# R650C.net
KiCad netlist of a schematic drawn in EAGLE
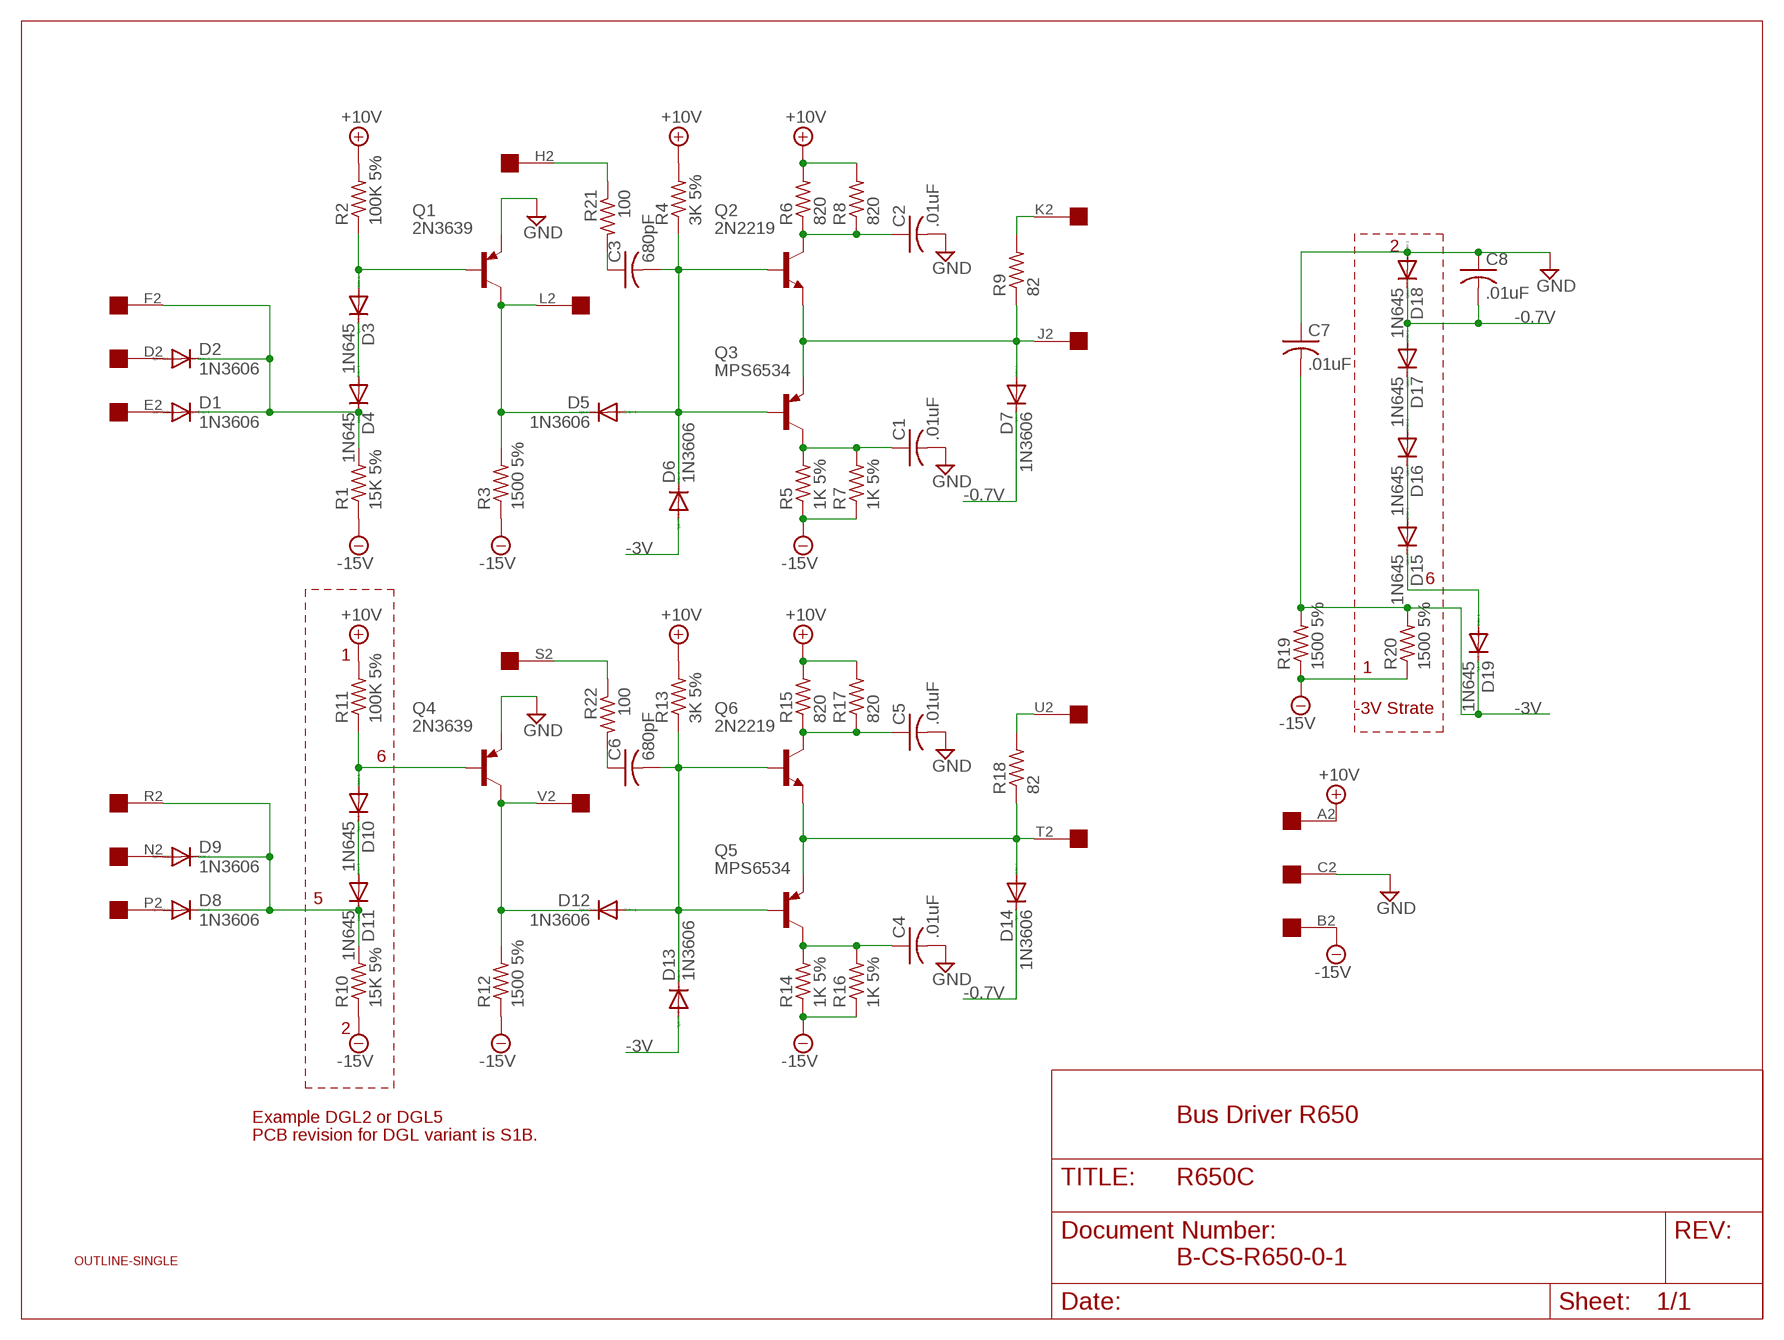
[diagram p0: schematic, sheet 1]

(export (version "E")
  (design (tool "Eeschema 10.0.6"))
  (components
    (comp (ref "C1")
      (value ".01uF")
      (footprint "eagle-import:C050-025X075")
      (libsource (lib "eagle-import") (part "C-US050-025X075"))
    )
    (comp (ref "C2")
      (value ".01uF")
      (footprint "eagle-import:C050-025X075")
      (libsource (lib "eagle-import") (part "C-US050-025X075"))
    )
    (comp (ref "C3")
      (value "680pF")
      (footprint "eagle-import:C050-025X075")
      (libsource (lib "eagle-import") (part "C-US050-025X075"))
    )
    (comp (ref "C4")
      (value ".01uF")
      (footprint "eagle-import:C050-025X075")
      (libsource (lib "eagle-import") (part "C-US050-025X075"))
    )
    (comp (ref "C5")
      (value ".01uF")
      (footprint "eagle-import:C050-025X075")
      (libsource (lib "eagle-import") (part "C-US050-025X075"))
    )
    (comp (ref "C6")
      (value "680pF")
      (footprint "eagle-import:C050-025X075")
      (libsource (lib "eagle-import") (part "C-US050-025X075"))
    )
    (comp (ref "C7")
      (value ".01uF")
      (footprint "eagle-import:C050-025X075")
      (libsource (lib "eagle-import") (part "C-US050-025X075"))
    )
    (comp (ref "C8")
      (value ".01uF")
      (footprint "eagle-import:C050-025X075")
      (libsource (lib "eagle-import") (part "C-US050-025X075"))
    )
    (comp (ref "D1")
      (value "1N3606")
      (footprint "eagle-import:DO35-10")
      (libsource (lib "eagle-import") (part "1N4148DO35-10"))
    )
    (comp (ref "D2")
      (value "1N3606")
      (footprint "eagle-import:DO35-10")
      (libsource (lib "eagle-import") (part "1N4148DO35-10"))
    )
    (comp (ref "D3")
      (value "1N645")
      (footprint "eagle-import:DO35-10")
      (libsource (lib "eagle-import") (part "1N4148DO35-10"))
    )
    (comp (ref "D4")
      (value "1N645")
      (footprint "eagle-import:DO35-10")
      (libsource (lib "eagle-import") (part "1N4148DO35-10"))
    )
    (comp (ref "D5")
      (value "1N3606")
      (footprint "eagle-import:DO35-10")
      (libsource (lib "eagle-import") (part "1N4148DO35-10"))
    )
    (comp (ref "D6")
      (value "1N3606")
      (footprint "eagle-import:DO35-10")
      (libsource (lib "eagle-import") (part "1N4148DO35-10"))
    )
    (comp (ref "D7")
      (value "1N3606")
      (footprint "eagle-import:DO35-10")
      (libsource (lib "eagle-import") (part "1N4148DO35-10"))
    )
    (comp (ref "D8")
      (value "1N3606")
      (footprint "eagle-import:DO35-10")
      (libsource (lib "eagle-import") (part "1N4148DO35-10"))
    )
    (comp (ref "D9")
      (value "1N3606")
      (footprint "eagle-import:DO35-10")
      (libsource (lib "eagle-import") (part "1N4148DO35-10"))
    )
    (comp (ref "D10")
      (value "1N645")
      (footprint "eagle-import:DO35-10")
      (libsource (lib "eagle-import") (part "1N4148DO35-10"))
    )
    (comp (ref "D11")
      (value "1N645")
      (footprint "eagle-import:DO35-10")
      (libsource (lib "eagle-import") (part "1N4148DO35-10"))
    )
    (comp (ref "D12")
      (value "1N3606")
      (footprint "eagle-import:DO35-10")
      (libsource (lib "eagle-import") (part "1N4148DO35-10"))
    )
    (comp (ref "D13")
      (value "1N3606")
      (footprint "eagle-import:DO35-10")
      (libsource (lib "eagle-import") (part "1N4148DO35-10"))
    )
    (comp (ref "D14")
      (value "1N3606")
      (footprint "eagle-import:DO35-10")
      (libsource (lib "eagle-import") (part "1N4148DO35-10"))
    )
    (comp (ref "D15")
      (value "1N645")
      (footprint "eagle-import:DO35-10")
      (libsource (lib "eagle-import") (part "1N4148DO35-10"))
    )
    (comp (ref "D16")
      (value "1N645")
      (footprint "eagle-import:DO35-10")
      (libsource (lib "eagle-import") (part "1N4148DO35-10"))
    )
    (comp (ref "D17")
      (value "1N645")
      (footprint "eagle-import:DO35-10")
      (libsource (lib "eagle-import") (part "1N4148DO35-10"))
    )
    (comp (ref "D18")
      (value "1N645")
      (footprint "eagle-import:DO35-10")
      (libsource (lib "eagle-import") (part "1N4148DO35-10"))
    )
    (comp (ref "D19")
      (value "1N645")
      (footprint "eagle-import:DO35-10")
      (libsource (lib "eagle-import") (part "1N4148DO35-10"))
    )
    (comp (ref "Q1")
      (value "2N3639")
      (footprint "eagle-import:TO39")
      (libsource (lib "eagle-import") (part "2N3637"))
    )
    (comp (ref "Q2")
      (value "2N2219")
      (footprint "eagle-import:TO5")
      (libsource (lib "eagle-import") (part "2N2219"))
    )
    (comp (ref "Q3")
      (value "MPS6534")
      (footprint "eagle-import:TO39")
      (libsource (lib "eagle-import") (part "2N3637"))
    )
    (comp (ref "Q4")
      (value "2N3639")
      (footprint "eagle-import:TO39")
      (libsource (lib "eagle-import") (part "2N3637"))
    )
    (comp (ref "Q5")
      (value "MPS6534")
      (footprint "eagle-import:TO39")
      (libsource (lib "eagle-import") (part "2N3637"))
    )
    (comp (ref "Q6")
      (value "2N2219")
      (footprint "eagle-import:TO5")
      (libsource (lib "eagle-import") (part "2N2219"))
    )
    (comp (ref "R1")
      (value "15K 5%")
      (footprint "eagle-import:0207_10")
      (libsource (lib "eagle-import") (part "R-US_0207/10"))
    )
    (comp (ref "R2")
      (value "100K 5%")
      (footprint "eagle-import:0207_10")
      (libsource (lib "eagle-import") (part "R-US_0207/10"))
    )
    (comp (ref "R3")
      (value "1500 5%")
      (footprint "eagle-import:0207_10")
      (libsource (lib "eagle-import") (part "R-US_0207/10"))
    )
    (comp (ref "R4")
      (value "3K 5%")
      (footprint "eagle-import:0207_10")
      (libsource (lib "eagle-import") (part "R-US_0207/10"))
    )
    (comp (ref "R5")
      (value "1K 5%")
      (footprint "eagle-import:0207_10")
      (libsource (lib "eagle-import") (part "R-US_0207/10"))
    )
    (comp (ref "R6")
      (value "820")
      (footprint "eagle-import:0207_10")
      (libsource (lib "eagle-import") (part "R-US_0207/10"))
    )
    (comp (ref "R7")
      (value "1K 5%")
      (footprint "eagle-import:0207_10")
      (libsource (lib "eagle-import") (part "R-US_0207/10"))
    )
    (comp (ref "R8")
      (value "820")
      (footprint "eagle-import:0207_10")
      (libsource (lib "eagle-import") (part "R-US_0207/10"))
    )
    (comp (ref "R9")
      (value "82")
      (footprint "eagle-import:0207_10")
      (libsource (lib "eagle-import") (part "R-US_0207/10"))
    )
    (comp (ref "R10")
      (value "15K 5%")
      (footprint "eagle-import:0207_10")
      (libsource (lib "eagle-import") (part "R-US_0207/10"))
    )
    (comp (ref "R11")
      (value "100K 5%")
      (footprint "eagle-import:0207_10")
      (libsource (lib "eagle-import") (part "R-US_0207/10"))
    )
    (comp (ref "R12")
      (value "1500 5%")
      (footprint "eagle-import:0207_10")
      (libsource (lib "eagle-import") (part "R-US_0207/10"))
    )
    (comp (ref "R13")
      (value "3K 5%")
      (footprint "eagle-import:0207_10")
      (libsource (lib "eagle-import") (part "R-US_0207/10"))
    )
    (comp (ref "R14")
      (value "1K 5%")
      (footprint "eagle-import:0207_10")
      (libsource (lib "eagle-import") (part "R-US_0207/10"))
    )
    (comp (ref "R15")
      (value "820")
      (footprint "eagle-import:0207_10")
      (libsource (lib "eagle-import") (part "R-US_0207/10"))
    )
    (comp (ref "R16")
      (value "1K 5%")
      (footprint "eagle-import:0207_10")
      (libsource (lib "eagle-import") (part "R-US_0207/10"))
    )
    (comp (ref "R17")
      (value "820")
      (footprint "eagle-import:0207_10")
      (libsource (lib "eagle-import") (part "R-US_0207/10"))
    )
    (comp (ref "R18")
      (value "82")
      (footprint "eagle-import:0207_10")
      (libsource (lib "eagle-import") (part "R-US_0207/10"))
    )
    (comp (ref "R19")
      (value "1500 5%")
      (footprint "eagle-import:0207_10")
      (libsource (lib "eagle-import") (part "R-US_0207/10"))
    )
    (comp (ref "R20")
      (value "1500 5%")
      (footprint "eagle-import:0207_10")
      (libsource (lib "eagle-import") (part "R-US_0207/10"))
    )
    (comp (ref "R21")
      (value "100")
      (footprint "eagle-import:0207_10")
      (libsource (lib "eagle-import") (part "R-US_0207/10"))
    )
    (comp (ref "R22")
      (value "100")
      (footprint "eagle-import:0207_10")
      (libsource (lib "eagle-import") (part "R-US_0207/10"))
    )
    (comp (ref "U$1")
      (value "OUTLINE-SINGLE")
      (footprint "eagle-import:SINGLE")
      (libsource (lib "eagle-import") (part "OUTLINE-SINGLE"))
    )
    (comp (ref "U$2")
      (value "EDGE-1")
      (footprint "eagle-import:EDGE-CON1")
      (libsource (lib "eagle-import") (part "EDGE-1"))
    )
  )
  (nets
    (net (code "1") (name "+10V") (class "Default")
      (node (ref "R11") (pin "2") (pinfunction "2_2") (pintype "passive"))
      (node (ref "R13") (pin "2") (pinfunction "2_2") (pintype "passive"))
      (node (ref "R15") (pin "2") (pinfunction "2_2") (pintype "passive"))
      (node (ref "R17") (pin "2") (pinfunction "2_2") (pintype "passive"))
      (node (ref "R2") (pin "2") (pinfunction "2_2") (pintype "passive"))
      (node (ref "R4") (pin "2") (pinfunction "2_2") (pintype "passive"))
      (node (ref "R6") (pin "2") (pinfunction "2_2") (pintype "passive"))
      (node (ref "R8") (pin "2") (pinfunction "2_2") (pintype "passive"))
      (node (ref "U$2") (pin "A2") (pinfunction "1_A2") (pintype "bidirectional"))
    )
    (net (code "2") (name "-15V") (class "Default")
      (node (ref "R1") (pin "1") (pinfunction "1_1") (pintype "passive"))
      (node (ref "R10") (pin "1") (pinfunction "1_1") (pintype "passive"))
      (node (ref "R12") (pin "1") (pinfunction "1_1") (pintype "passive"))
      (node (ref "R14") (pin "1") (pinfunction "1_1") (pintype "passive"))
      (node (ref "R16") (pin "1") (pinfunction "1_1") (pintype "passive"))
      (node (ref "R19") (pin "1") (pinfunction "1_1") (pintype "passive"))
      (node (ref "R20") (pin "1") (pinfunction "1_1") (pintype "passive"))
      (node (ref "R3") (pin "1") (pinfunction "1_1") (pintype "passive"))
      (node (ref "R5") (pin "1") (pinfunction "1_1") (pintype "passive"))
      (node (ref "R7") (pin "1") (pinfunction "1_1") (pintype "passive"))
      (node (ref "U$2") (pin "B2") (pinfunction "1_B2") (pintype "bidirectional"))
    )
    (net (code "3") (name "/-0.7V") (class "Default")
      (node (ref "C8") (pin "2") (pinfunction "2_2") (pintype "passive"))
      (node (ref "D14") (pin "C") (pinfunction "C_C") (pintype "passive"))
      (node (ref "D17") (pin "A") (pinfunction "A_A") (pintype "passive"))
      (node (ref "D18") (pin "C") (pinfunction "C_C") (pintype "passive"))
      (node (ref "D7") (pin "C") (pinfunction "C_C") (pintype "passive"))
    )
    (net (code "4") (name "/-3V") (class "Default")
      (node (ref "C7") (pin "2") (pinfunction "2_2") (pintype "passive"))
      (node (ref "D13") (pin "A") (pinfunction "A_A") (pintype "passive"))
      (node (ref "D19") (pin "C") (pinfunction "C_C") (pintype "passive"))
      (node (ref "D6") (pin "A") (pinfunction "A_A") (pintype "passive"))
      (node (ref "R19") (pin "2") (pinfunction "2_2") (pintype "passive"))
      (node (ref "R20") (pin "2") (pinfunction "2_2") (pintype "passive"))
    )
    (net (code "5") (name "GND") (class "Default")
      (node (ref "C1") (pin "2") (pinfunction "2_2") (pintype "passive"))
      (node (ref "C2") (pin "2") (pinfunction "2_2") (pintype "passive"))
      (node (ref "C4") (pin "2") (pinfunction "2_2") (pintype "passive"))
      (node (ref "C5") (pin "2") (pinfunction "2_2") (pintype "passive"))
      (node (ref "C7") (pin "1") (pinfunction "1_1") (pintype "passive"))
      (node (ref "C8") (pin "1") (pinfunction "1_1") (pintype "passive"))
      (node (ref "D18") (pin "A") (pinfunction "A_A") (pintype "passive"))
      (node (ref "Q1") (pin "1") (pinfunction "E_1") (pintype "passive"))
      (node (ref "Q4") (pin "1") (pinfunction "E_1") (pintype "passive"))
      (node (ref "U$2") (pin "C2") (pinfunction "1_C2") (pintype "bidirectional"))
    )
    (net (code "6") (name "Net-(C3-Pad1)") (class "Default")
      (node (ref "C3") (pin "1") (pinfunction "1_1") (pintype "passive"))
      (node (ref "R21") (pin "2") (pinfunction "2_2") (pintype "passive"))
    )
    (net (code "7") (name "Net-(C6-Pad1)") (class "Default")
      (node (ref "C6") (pin "1") (pinfunction "1_1") (pintype "passive"))
      (node (ref "R22") (pin "2") (pinfunction "2_2") (pintype "passive"))
    )
    (net (code "8") (name "Net-(D3-PadC)") (class "Default")
      (node (ref "D3") (pin "C") (pinfunction "C_C") (pintype "passive"))
      (node (ref "D4") (pin "A") (pinfunction "A_A") (pintype "passive"))
    )
    (net (code "9") (name "Net-(D10-PadC)") (class "Default")
      (node (ref "D10") (pin "C") (pinfunction "C_C") (pintype "passive"))
      (node (ref "D11") (pin "A") (pinfunction "A_A") (pintype "passive"))
    )
    (net (code "10") (name "Net-(D15-PadA)") (class "Default")
      (node (ref "D15") (pin "A") (pinfunction "A_A") (pintype "passive"))
      (node (ref "D16") (pin "C") (pinfunction "C_C") (pintype "passive"))
    )
    (net (code "11") (name "Net-(D15-PadC)") (class "Default")
      (node (ref "D15") (pin "C") (pinfunction "C_C") (pintype "passive"))
      (node (ref "D19") (pin "A") (pinfunction "A_A") (pintype "passive"))
    )
    (net (code "12") (name "Net-(D16-PadA)") (class "Default")
      (node (ref "D16") (pin "A") (pinfunction "A_A") (pintype "passive"))
      (node (ref "D17") (pin "C") (pinfunction "C_C") (pintype "passive"))
    )
    (net (code "13") (name "Net-(Q1-B)") (class "Default")
      (node (ref "D3") (pin "A") (pinfunction "A_A") (pintype "passive"))
      (node (ref "Q1") (pin "2") (pinfunction "B_2") (pintype "passive"))
      (node (ref "R2") (pin "1") (pinfunction "1_1") (pintype "passive"))
    )
    (net (code "14") (name "Net-(Q1-C)") (class "Default")
      (node (ref "D5") (pin "C") (pinfunction "C_C") (pintype "passive"))
      (node (ref "Q1") (pin "3") (pinfunction "C_3") (pintype "passive"))
      (node (ref "R3") (pin "2") (pinfunction "2_2") (pintype "passive"))
      (node (ref "U$2") (pin "L2") (pinfunction "1_L2") (pintype "bidirectional"))
    )
    (net (code "15") (name "Net-(Q2-B)") (class "Default")
      (node (ref "C3") (pin "2") (pinfunction "2_2") (pintype "passive"))
      (node (ref "D5") (pin "A") (pinfunction "A_A") (pintype "passive"))
      (node (ref "D6") (pin "C") (pinfunction "C_C") (pintype "passive"))
      (node (ref "Q2") (pin "2") (pinfunction "B_2") (pintype "passive"))
      (node (ref "Q3") (pin "2") (pinfunction "B_2") (pintype "passive"))
      (node (ref "R4") (pin "1") (pinfunction "1_1") (pintype "passive"))
    )
    (net (code "16") (name "Net-(Q2-C)") (class "Default")
      (node (ref "C2") (pin "1") (pinfunction "1_1") (pintype "passive"))
      (node (ref "Q2") (pin "3") (pinfunction "C_3") (pintype "passive"))
      (node (ref "R6") (pin "1") (pinfunction "1_1") (pintype "passive"))
      (node (ref "R8") (pin "1") (pinfunction "1_1") (pintype "passive"))
    )
    (net (code "17") (name "Net-(Q2-E)") (class "Default")
      (node (ref "D7") (pin "A") (pinfunction "A_A") (pintype "passive"))
      (node (ref "Q2") (pin "1") (pinfunction "E_1") (pintype "passive"))
      (node (ref "Q3") (pin "1") (pinfunction "E_1") (pintype "passive"))
      (node (ref "R9") (pin "1") (pinfunction "1_1") (pintype "passive"))
      (node (ref "U$2") (pin "J2") (pinfunction "1_J2") (pintype "bidirectional"))
    )
    (net (code "18") (name "Net-(Q3-C)") (class "Default")
      (node (ref "C1") (pin "1") (pinfunction "1_1") (pintype "passive"))
      (node (ref "Q3") (pin "3") (pinfunction "C_3") (pintype "passive"))
      (node (ref "R5") (pin "2") (pinfunction "2_2") (pintype "passive"))
      (node (ref "R7") (pin "2") (pinfunction "2_2") (pintype "passive"))
    )
    (net (code "19") (name "Net-(Q4-B)") (class "Default")
      (node (ref "D10") (pin "A") (pinfunction "A_A") (pintype "passive"))
      (node (ref "Q4") (pin "2") (pinfunction "B_2") (pintype "passive"))
      (node (ref "R11") (pin "1") (pinfunction "1_1") (pintype "passive"))
    )
    (net (code "20") (name "Net-(Q4-C)") (class "Default")
      (node (ref "D12") (pin "C") (pinfunction "C_C") (pintype "passive"))
      (node (ref "Q4") (pin "3") (pinfunction "C_3") (pintype "passive"))
      (node (ref "R12") (pin "2") (pinfunction "2_2") (pintype "passive"))
      (node (ref "U$2") (pin "V2") (pinfunction "1_V2") (pintype "bidirectional"))
    )
    (net (code "21") (name "Net-(Q5-B)") (class "Default")
      (node (ref "C6") (pin "2") (pinfunction "2_2") (pintype "passive"))
      (node (ref "D12") (pin "A") (pinfunction "A_A") (pintype "passive"))
      (node (ref "D13") (pin "C") (pinfunction "C_C") (pintype "passive"))
      (node (ref "Q5") (pin "2") (pinfunction "B_2") (pintype "passive"))
      (node (ref "Q6") (pin "2") (pinfunction "B_2") (pintype "passive"))
      (node (ref "R13") (pin "1") (pinfunction "1_1") (pintype "passive"))
    )
    (net (code "22") (name "Net-(Q5-C)") (class "Default")
      (node (ref "C4") (pin "1") (pinfunction "1_1") (pintype "passive"))
      (node (ref "Q5") (pin "3") (pinfunction "C_3") (pintype "passive"))
      (node (ref "R14") (pin "2") (pinfunction "2_2") (pintype "passive"))
      (node (ref "R16") (pin "2") (pinfunction "2_2") (pintype "passive"))
    )
    (net (code "23") (name "Net-(Q5-E)") (class "Default")
      (node (ref "D14") (pin "A") (pinfunction "A_A") (pintype "passive"))
      (node (ref "Q5") (pin "1") (pinfunction "E_1") (pintype "passive"))
      (node (ref "Q6") (pin "1") (pinfunction "E_1") (pintype "passive"))
      (node (ref "R18") (pin "1") (pinfunction "1_1") (pintype "passive"))
      (node (ref "U$2") (pin "T2") (pinfunction "1_T2") (pintype "bidirectional"))
    )
    (net (code "24") (name "Net-(Q6-C)") (class "Default")
      (node (ref "C5") (pin "1") (pinfunction "1_1") (pintype "passive"))
      (node (ref "Q6") (pin "3") (pinfunction "C_3") (pintype "passive"))
      (node (ref "R15") (pin "1") (pinfunction "1_1") (pintype "passive"))
      (node (ref "R17") (pin "1") (pinfunction "1_1") (pintype "passive"))
    )
    (net (code "25") (name "Net-(U$2D-1)") (class "Default")
      (node (ref "D2") (pin "A") (pinfunction "A_A") (pintype "passive"))
      (node (ref "U$2") (pin "D2") (pinfunction "1_D2") (pintype "bidirectional"))
    )
    (net (code "26") (name "Net-(U$2E-1)") (class "Default")
      (node (ref "D1") (pin "A") (pinfunction "A_A") (pintype "passive"))
      (node (ref "U$2") (pin "E2") (pinfunction "1_E2") (pintype "bidirectional"))
    )
    (net (code "27") (name "Net-(U$2F-1)") (class "Default")
      (node (ref "D1") (pin "C") (pinfunction "C_C") (pintype "passive"))
      (node (ref "D2") (pin "C") (pinfunction "C_C") (pintype "passive"))
      (node (ref "D4") (pin "C") (pinfunction "C_C") (pintype "passive"))
      (node (ref "R1") (pin "2") (pinfunction "2_2") (pintype "passive"))
      (node (ref "U$2") (pin "F2") (pinfunction "1_F2") (pintype "bidirectional"))
    )
    (net (code "28") (name "Net-(U$2G-1)") (class "Default")
      (node (ref "R21") (pin "1") (pinfunction "1_1") (pintype "passive"))
      (node (ref "U$2") (pin "H2") (pinfunction "1_H2") (pintype "bidirectional"))
    )
    (net (code "29") (name "Net-(U$2I-1)") (class "Default")
      (node (ref "R9") (pin "2") (pinfunction "2_2") (pintype "passive"))
      (node (ref "U$2") (pin "K2") (pinfunction "1_K2") (pintype "bidirectional"))
    )
    (net (code "30") (name "Net-(U$2L-1)") (class "Default")
      (node (ref "D9") (pin "A") (pinfunction "A_A") (pintype "passive"))
      (node (ref "U$2") (pin "N2") (pinfunction "1_N2") (pintype "bidirectional"))
    )
    (net (code "31") (name "Net-(U$2M-1)") (class "Default")
      (node (ref "D8") (pin "A") (pinfunction "A_A") (pintype "passive"))
      (node (ref "U$2") (pin "P2") (pinfunction "1_P2") (pintype "bidirectional"))
    )
    (net (code "32") (name "Net-(U$2N-1)") (class "Default")
      (node (ref "D11") (pin "C") (pinfunction "C_C") (pintype "passive"))
      (node (ref "D8") (pin "C") (pinfunction "C_C") (pintype "passive"))
      (node (ref "D9") (pin "C") (pinfunction "C_C") (pintype "passive"))
      (node (ref "R10") (pin "2") (pinfunction "2_2") (pintype "passive"))
      (node (ref "U$2") (pin "R2") (pinfunction "1_R2") (pintype "bidirectional"))
    )
    (net (code "33") (name "Net-(U$2O-1)") (class "Default")
      (node (ref "R22") (pin "1") (pinfunction "1_1") (pintype "passive"))
      (node (ref "U$2") (pin "S2") (pinfunction "1_S2") (pintype "bidirectional"))
    )
    (net (code "34") (name "Net-(U$2Q-1)") (class "Default")
      (node (ref "R18") (pin "2") (pinfunction "2_2") (pintype "passive"))
      (node (ref "U$2") (pin "U2") (pinfunction "1_U2") (pintype "bidirectional"))
    )
  )
)
